# micro_motor.net
KiCad netlist of a schematic drawn in EAGLE
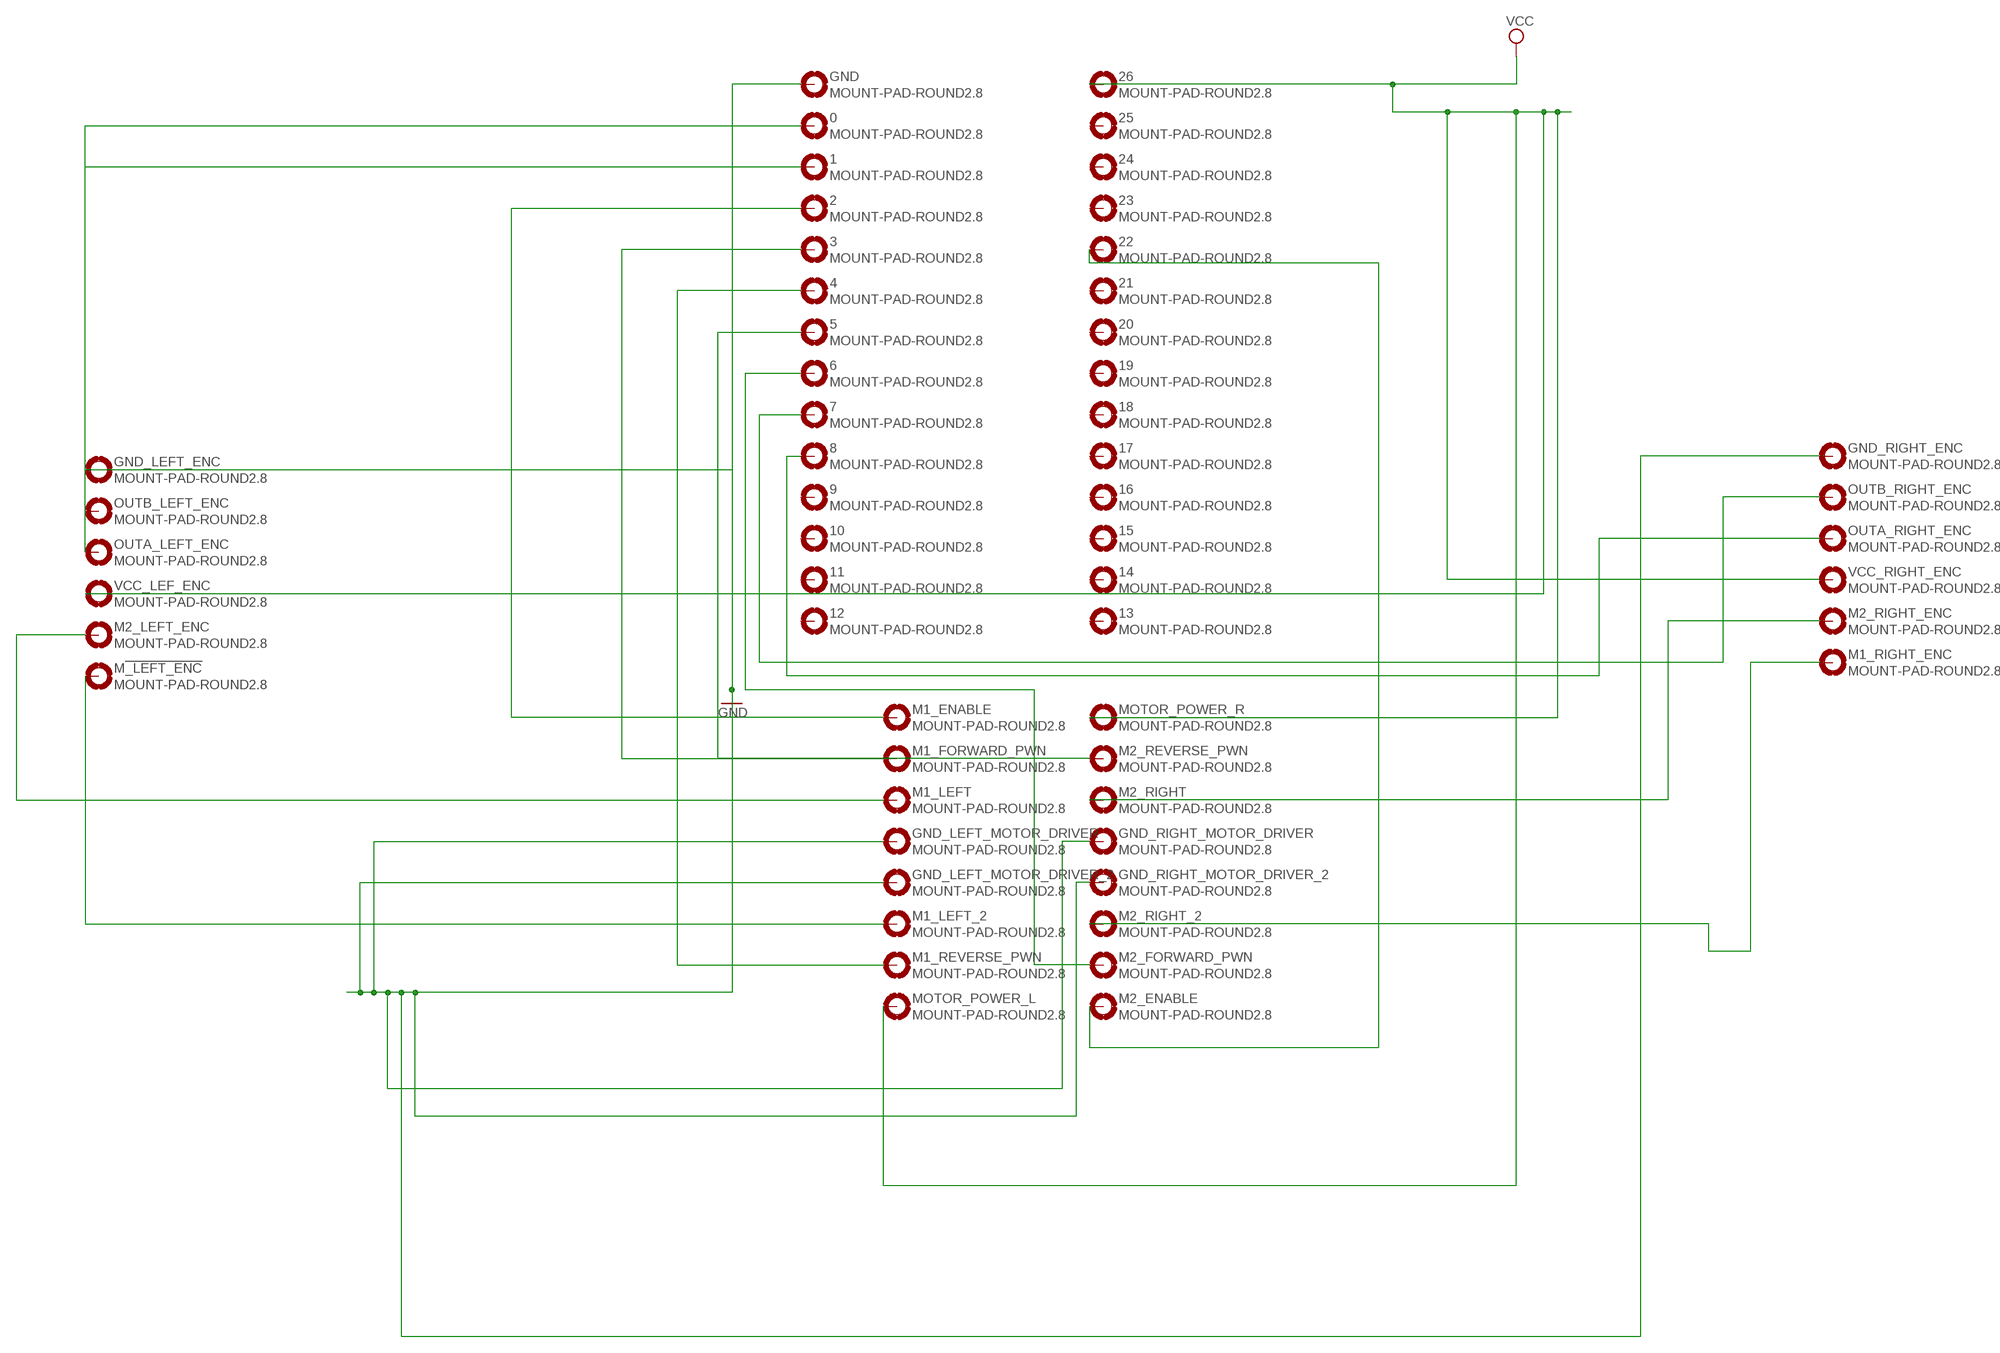
[diagram p0: schematic, sheet 1]

(export (version "E")
  (design (tool "Eeschema 10.0.6"))
  (components
    (comp (ref "0")
      (value "MOUNT-PAD-ROUND2.8")
      (footprint "eagle-import:2,8-PAD")
      (libsource (lib "eagle-import") (part "MOUNT-PAD-ROUND2.8"))
    )
    (comp (ref "1")
      (value "MOUNT-PAD-ROUND2.8")
      (footprint "eagle-import:2,8-PAD")
      (libsource (lib "eagle-import") (part "MOUNT-PAD-ROUND2.8"))
    )
    (comp (ref "2")
      (value "MOUNT-PAD-ROUND2.8")
      (footprint "eagle-import:2,8-PAD")
      (libsource (lib "eagle-import") (part "MOUNT-PAD-ROUND2.8"))
    )
    (comp (ref "3")
      (value "MOUNT-PAD-ROUND2.8")
      (footprint "eagle-import:2,8-PAD")
      (libsource (lib "eagle-import") (part "MOUNT-PAD-ROUND2.8"))
    )
    (comp (ref "4")
      (value "MOUNT-PAD-ROUND2.8")
      (footprint "eagle-import:2,8-PAD")
      (libsource (lib "eagle-import") (part "MOUNT-PAD-ROUND2.8"))
    )
    (comp (ref "5")
      (value "MOUNT-PAD-ROUND2.8")
      (footprint "eagle-import:2,8-PAD")
      (libsource (lib "eagle-import") (part "MOUNT-PAD-ROUND2.8"))
    )
    (comp (ref "6")
      (value "MOUNT-PAD-ROUND2.8")
      (footprint "eagle-import:2,8-PAD")
      (libsource (lib "eagle-import") (part "MOUNT-PAD-ROUND2.8"))
    )
    (comp (ref "7")
      (value "MOUNT-PAD-ROUND2.8")
      (footprint "eagle-import:2,8-PAD")
      (libsource (lib "eagle-import") (part "MOUNT-PAD-ROUND2.8"))
    )
    (comp (ref "8")
      (value "MOUNT-PAD-ROUND2.8")
      (footprint "eagle-import:2,8-PAD")
      (libsource (lib "eagle-import") (part "MOUNT-PAD-ROUND2.8"))
    )
    (comp (ref "9")
      (value "MOUNT-PAD-ROUND2.8")
      (footprint "eagle-import:2,8-PAD")
      (libsource (lib "eagle-import") (part "MOUNT-PAD-ROUND2.8"))
    )
    (comp (ref "10")
      (value "MOUNT-PAD-ROUND2.8")
      (footprint "eagle-import:2,8-PAD")
      (libsource (lib "eagle-import") (part "MOUNT-PAD-ROUND2.8"))
    )
    (comp (ref "11")
      (value "MOUNT-PAD-ROUND2.8")
      (footprint "eagle-import:2,8-PAD")
      (libsource (lib "eagle-import") (part "MOUNT-PAD-ROUND2.8"))
    )
    (comp (ref "12")
      (value "MOUNT-PAD-ROUND2.8")
      (footprint "eagle-import:2,8-PAD")
      (libsource (lib "eagle-import") (part "MOUNT-PAD-ROUND2.8"))
    )
    (comp (ref "13")
      (value "MOUNT-PAD-ROUND2.8")
      (footprint "eagle-import:2,8-PAD")
      (libsource (lib "eagle-import") (part "MOUNT-PAD-ROUND2.8"))
    )
    (comp (ref "14")
      (value "MOUNT-PAD-ROUND2.8")
      (footprint "eagle-import:2,8-PAD")
      (libsource (lib "eagle-import") (part "MOUNT-PAD-ROUND2.8"))
    )
    (comp (ref "15")
      (value "MOUNT-PAD-ROUND2.8")
      (footprint "eagle-import:2,8-PAD")
      (libsource (lib "eagle-import") (part "MOUNT-PAD-ROUND2.8"))
    )
    (comp (ref "16")
      (value "MOUNT-PAD-ROUND2.8")
      (footprint "eagle-import:2,8-PAD")
      (libsource (lib "eagle-import") (part "MOUNT-PAD-ROUND2.8"))
    )
    (comp (ref "17")
      (value "MOUNT-PAD-ROUND2.8")
      (footprint "eagle-import:2,8-PAD")
      (libsource (lib "eagle-import") (part "MOUNT-PAD-ROUND2.8"))
    )
    (comp (ref "18")
      (value "MOUNT-PAD-ROUND2.8")
      (footprint "eagle-import:2,8-PAD")
      (libsource (lib "eagle-import") (part "MOUNT-PAD-ROUND2.8"))
    )
    (comp (ref "19")
      (value "MOUNT-PAD-ROUND2.8")
      (footprint "eagle-import:2,8-PAD")
      (libsource (lib "eagle-import") (part "MOUNT-PAD-ROUND2.8"))
    )
    (comp (ref "20")
      (value "MOUNT-PAD-ROUND2.8")
      (footprint "eagle-import:2,8-PAD")
      (libsource (lib "eagle-import") (part "MOUNT-PAD-ROUND2.8"))
    )
    (comp (ref "21")
      (value "MOUNT-PAD-ROUND2.8")
      (footprint "eagle-import:2,8-PAD")
      (libsource (lib "eagle-import") (part "MOUNT-PAD-ROUND2.8"))
    )
    (comp (ref "22")
      (value "MOUNT-PAD-ROUND2.8")
      (footprint "eagle-import:2,8-PAD")
      (libsource (lib "eagle-import") (part "MOUNT-PAD-ROUND2.8"))
    )
    (comp (ref "23")
      (value "MOUNT-PAD-ROUND2.8")
      (footprint "eagle-import:2,8-PAD")
      (libsource (lib "eagle-import") (part "MOUNT-PAD-ROUND2.8"))
    )
    (comp (ref "24")
      (value "MOUNT-PAD-ROUND2.8")
      (footprint "eagle-import:2,8-PAD")
      (libsource (lib "eagle-import") (part "MOUNT-PAD-ROUND2.8"))
    )
    (comp (ref "25")
      (value "MOUNT-PAD-ROUND2.8")
      (footprint "eagle-import:2,8-PAD")
      (libsource (lib "eagle-import") (part "MOUNT-PAD-ROUND2.8"))
    )
    (comp (ref "26")
      (value "MOUNT-PAD-ROUND2.8")
      (footprint "eagle-import:2,8-PAD")
      (libsource (lib "eagle-import") (part "MOUNT-PAD-ROUND2.8"))
    )
    (comp (ref "GND")
      (value "MOUNT-PAD-ROUND2.8")
      (footprint "eagle-import:2,8-PAD")
      (libsource (lib "eagle-import") (part "MOUNT-PAD-ROUND2.8"))
    )
    (comp (ref "GND_LEFT_ENC")
      (value "MOUNT-PAD-ROUND2.8")
      (footprint "eagle-import:2,8-PAD")
      (libsource (lib "eagle-import") (part "MOUNT-PAD-ROUND2.8"))
    )
    (comp (ref "GND_LEFT_MOTOR_DRIVER")
      (value "MOUNT-PAD-ROUND2.8")
      (footprint "eagle-import:2,8-PAD")
      (libsource (lib "eagle-import") (part "MOUNT-PAD-ROUND2.8"))
    )
    (comp (ref "GND_LEFT_MOTOR_DRIVER_2")
      (value "MOUNT-PAD-ROUND2.8")
      (footprint "eagle-import:2,8-PAD")
      (libsource (lib "eagle-import") (part "MOUNT-PAD-ROUND2.8"))
    )
    (comp (ref "GND_RIGHT_ENC")
      (value "MOUNT-PAD-ROUND2.8")
      (footprint "eagle-import:2,8-PAD")
      (libsource (lib "eagle-import") (part "MOUNT-PAD-ROUND2.8"))
    )
    (comp (ref "GND_RIGHT_MOTOR_DRIVER")
      (value "MOUNT-PAD-ROUND2.8")
      (footprint "eagle-import:2,8-PAD")
      (libsource (lib "eagle-import") (part "MOUNT-PAD-ROUND2.8"))
    )
    (comp (ref "GND_RIGHT_MOTOR_DRIVER_2")
      (value "MOUNT-PAD-ROUND2.8")
      (footprint "eagle-import:2,8-PAD")
      (libsource (lib "eagle-import") (part "MOUNT-PAD-ROUND2.8"))
    )
    (comp (ref "M!_LEFT_ENC")
      (value "MOUNT-PAD-ROUND2.8")
      (footprint "eagle-import:2,8-PAD")
      (libsource (lib "eagle-import") (part "MOUNT-PAD-ROUND2.8"))
    )
    (comp (ref "M1_ENABLE")
      (value "MOUNT-PAD-ROUND2.8")
      (footprint "eagle-import:2,8-PAD")
      (libsource (lib "eagle-import") (part "MOUNT-PAD-ROUND2.8"))
    )
    (comp (ref "M1_FORWARD_PWN")
      (value "MOUNT-PAD-ROUND2.8")
      (footprint "eagle-import:2,8-PAD")
      (libsource (lib "eagle-import") (part "MOUNT-PAD-ROUND2.8"))
    )
    (comp (ref "M1_LEFT")
      (value "MOUNT-PAD-ROUND2.8")
      (footprint "eagle-import:2,8-PAD")
      (libsource (lib "eagle-import") (part "MOUNT-PAD-ROUND2.8"))
    )
    (comp (ref "M1_LEFT_2")
      (value "MOUNT-PAD-ROUND2.8")
      (footprint "eagle-import:2,8-PAD")
      (libsource (lib "eagle-import") (part "MOUNT-PAD-ROUND2.8"))
    )
    (comp (ref "M1_REVERSE_PWN")
      (value "MOUNT-PAD-ROUND2.8")
      (footprint "eagle-import:2,8-PAD")
      (libsource (lib "eagle-import") (part "MOUNT-PAD-ROUND2.8"))
    )
    (comp (ref "M1_RIGHT_ENC")
      (value "MOUNT-PAD-ROUND2.8")
      (footprint "eagle-import:2,8-PAD")
      (libsource (lib "eagle-import") (part "MOUNT-PAD-ROUND2.8"))
    )
    (comp (ref "M2_ENABLE")
      (value "MOUNT-PAD-ROUND2.8")
      (footprint "eagle-import:2,8-PAD")
      (libsource (lib "eagle-import") (part "MOUNT-PAD-ROUND2.8"))
    )
    (comp (ref "M2_FORWARD_PWN")
      (value "MOUNT-PAD-ROUND2.8")
      (footprint "eagle-import:2,8-PAD")
      (libsource (lib "eagle-import") (part "MOUNT-PAD-ROUND2.8"))
    )
    (comp (ref "M2_LEFT_ENC")
      (value "MOUNT-PAD-ROUND2.8")
      (footprint "eagle-import:2,8-PAD")
      (libsource (lib "eagle-import") (part "MOUNT-PAD-ROUND2.8"))
    )
    (comp (ref "M2_REVERSE_PWN")
      (value "MOUNT-PAD-ROUND2.8")
      (footprint "eagle-import:2,8-PAD")
      (libsource (lib "eagle-import") (part "MOUNT-PAD-ROUND2.8"))
    )
    (comp (ref "M2_RIGHT")
      (value "MOUNT-PAD-ROUND2.8")
      (footprint "eagle-import:2,8-PAD")
      (libsource (lib "eagle-import") (part "MOUNT-PAD-ROUND2.8"))
    )
    (comp (ref "M2_RIGHT_2")
      (value "MOUNT-PAD-ROUND2.8")
      (footprint "eagle-import:2,8-PAD")
      (libsource (lib "eagle-import") (part "MOUNT-PAD-ROUND2.8"))
    )
    (comp (ref "M2_RIGHT_ENC")
      (value "MOUNT-PAD-ROUND2.8")
      (footprint "eagle-import:2,8-PAD")
      (libsource (lib "eagle-import") (part "MOUNT-PAD-ROUND2.8"))
    )
    (comp (ref "MOTOR_POWER_L")
      (value "MOUNT-PAD-ROUND2.8")
      (footprint "eagle-import:2,8-PAD")
      (libsource (lib "eagle-import") (part "MOUNT-PAD-ROUND2.8"))
    )
    (comp (ref "MOTOR_POWER_R")
      (value "MOUNT-PAD-ROUND2.8")
      (footprint "eagle-import:2,8-PAD")
      (libsource (lib "eagle-import") (part "MOUNT-PAD-ROUND2.8"))
    )
    (comp (ref "OUTA_LEFT_ENC")
      (value "MOUNT-PAD-ROUND2.8")
      (footprint "eagle-import:2,8-PAD")
      (libsource (lib "eagle-import") (part "MOUNT-PAD-ROUND2.8"))
    )
    (comp (ref "OUTA_RIGHT_ENC")
      (value "MOUNT-PAD-ROUND2.8")
      (footprint "eagle-import:2,8-PAD")
      (libsource (lib "eagle-import") (part "MOUNT-PAD-ROUND2.8"))
    )
    (comp (ref "OUTB_LEFT_ENC")
      (value "MOUNT-PAD-ROUND2.8")
      (footprint "eagle-import:2,8-PAD")
      (libsource (lib "eagle-import") (part "MOUNT-PAD-ROUND2.8"))
    )
    (comp (ref "OUTB_RIGHT_ENC")
      (value "MOUNT-PAD-ROUND2.8")
      (footprint "eagle-import:2,8-PAD")
      (libsource (lib "eagle-import") (part "MOUNT-PAD-ROUND2.8"))
    )
    (comp (ref "VCC_LEF_ENC")
      (value "MOUNT-PAD-ROUND2.8")
      (footprint "eagle-import:2,8-PAD")
      (libsource (lib "eagle-import") (part "MOUNT-PAD-ROUND2.8"))
    )
    (comp (ref "VCC_RIGHT_ENC")
      (value "MOUNT-PAD-ROUND2.8")
      (footprint "eagle-import:2,8-PAD")
      (libsource (lib "eagle-import") (part "MOUNT-PAD-ROUND2.8"))
    )
  )
  (nets
    (net (code "1") (name "GND") (class "Default")
      (node (ref "GND") (pin "B2,8") (pinfunction "MOUNT_B2,8") (pintype "passive"))
      (node (ref "GND_LEFT_ENC") (pin "B2,8") (pinfunction "MOUNT_B2,8") (pintype "passive"))
      (node (ref "GND_LEFT_MOTOR_DRIVER") (pin "B2,8") (pinfunction "MOUNT_B2,8") (pintype "passive"))
      (node (ref "GND_LEFT_MOTOR_DRIVER_2") (pin "B2,8") (pinfunction "MOUNT_B2,8") (pintype "passive"))
      (node (ref "GND_RIGHT_ENC") (pin "B2,8") (pinfunction "MOUNT_B2,8") (pintype "passive"))
      (node (ref "GND_RIGHT_MOTOR_DRIVER") (pin "B2,8") (pinfunction "MOUNT_B2,8") (pintype "passive"))
      (node (ref "GND_RIGHT_MOTOR_DRIVER_2") (pin "B2,8") (pinfunction "MOUNT_B2,8") (pintype "passive"))
    )
    (net (code "2") (name "Net-(0-MOUNT)") (class "Default")
      (node (ref "0") (pin "B2,8") (pinfunction "MOUNT_B2,8") (pintype "passive"))
      (node (ref "OUTB_LEFT_ENC") (pin "B2,8") (pinfunction "MOUNT_B2,8") (pintype "passive"))
    )
    (net (code "3") (name "Net-(1-MOUNT)") (class "Default")
      (node (ref "1") (pin "B2,8") (pinfunction "MOUNT_B2,8") (pintype "passive"))
      (node (ref "OUTA_LEFT_ENC") (pin "B2,8") (pinfunction "MOUNT_B2,8") (pintype "passive"))
    )
    (net (code "4") (name "Net-(2-MOUNT)") (class "Default")
      (node (ref "2") (pin "B2,8") (pinfunction "MOUNT_B2,8") (pintype "passive"))
      (node (ref "M1_ENABLE") (pin "B2,8") (pinfunction "MOUNT_B2,8") (pintype "passive"))
    )
    (net (code "5") (name "Net-(3-MOUNT)") (class "Default")
      (node (ref "3") (pin "B2,8") (pinfunction "MOUNT_B2,8") (pintype "passive"))
      (node (ref "M1_FORWARD_PWN") (pin "B2,8") (pinfunction "MOUNT_B2,8") (pintype "passive"))
    )
    (net (code "6") (name "Net-(4-MOUNT)") (class "Default")
      (node (ref "4") (pin "B2,8") (pinfunction "MOUNT_B2,8") (pintype "passive"))
      (node (ref "M1_REVERSE_PWN") (pin "B2,8") (pinfunction "MOUNT_B2,8") (pintype "passive"))
    )
    (net (code "7") (name "Net-(5-MOUNT)") (class "Default")
      (node (ref "5") (pin "B2,8") (pinfunction "MOUNT_B2,8") (pintype "passive"))
      (node (ref "M2_REVERSE_PWN") (pin "B2,8") (pinfunction "MOUNT_B2,8") (pintype "passive"))
    )
    (net (code "8") (name "Net-(6-MOUNT)") (class "Default")
      (node (ref "6") (pin "B2,8") (pinfunction "MOUNT_B2,8") (pintype "passive"))
      (node (ref "M2_FORWARD_PWN") (pin "B2,8") (pinfunction "MOUNT_B2,8") (pintype "passive"))
    )
    (net (code "9") (name "Net-(7-MOUNT)") (class "Default")
      (node (ref "7") (pin "B2,8") (pinfunction "MOUNT_B2,8") (pintype "passive"))
      (node (ref "OUTB_RIGHT_ENC") (pin "B2,8") (pinfunction "MOUNT_B2,8") (pintype "passive"))
    )
    (net (code "10") (name "Net-(8-MOUNT)") (class "Default")
      (node (ref "8") (pin "B2,8") (pinfunction "MOUNT_B2,8") (pintype "passive"))
      (node (ref "OUTA_RIGHT_ENC") (pin "B2,8") (pinfunction "MOUNT_B2,8") (pintype "passive"))
    )
    (net (code "11") (name "Net-(22-MOUNT)") (class "Default")
      (node (ref "22") (pin "B2,8") (pinfunction "MOUNT_B2,8") (pintype "passive"))
      (node (ref "M2_ENABLE") (pin "B2,8") (pinfunction "MOUNT_B2,8") (pintype "passive"))
    )
    (net (code "12") (name "Net-(M!_LEFT_ENC-MOUNT)") (class "Default")
      (node (ref "M!_LEFT_ENC") (pin "B2,8") (pinfunction "MOUNT_B2,8") (pintype "passive"))
      (node (ref "M1_LEFT_2") (pin "B2,8") (pinfunction "MOUNT_B2,8") (pintype "passive"))
    )
    (net (code "13") (name "Net-(M1_LEFT-MOUNT)") (class "Default")
      (node (ref "M1_LEFT") (pin "B2,8") (pinfunction "MOUNT_B2,8") (pintype "passive"))
      (node (ref "M2_LEFT_ENC") (pin "B2,8") (pinfunction "MOUNT_B2,8") (pintype "passive"))
    )
    (net (code "14") (name "Net-(M1_RIGHT_ENC-MOUNT)") (class "Default")
      (node (ref "M1_RIGHT_ENC") (pin "B2,8") (pinfunction "MOUNT_B2,8") (pintype "passive"))
      (node (ref "M2_RIGHT_2") (pin "B2,8") (pinfunction "MOUNT_B2,8") (pintype "passive"))
    )
    (net (code "15") (name "Net-(M2_RIGHT-MOUNT)") (class "Default")
      (node (ref "M2_RIGHT") (pin "B2,8") (pinfunction "MOUNT_B2,8") (pintype "passive"))
      (node (ref "M2_RIGHT_ENC") (pin "B2,8") (pinfunction "MOUNT_B2,8") (pintype "passive"))
    )
    (net (code "16") (name "VCC") (class "Default")
      (node (ref "26") (pin "B2,8") (pinfunction "MOUNT_B2,8") (pintype "passive"))
      (node (ref "MOTOR_POWER_L") (pin "B2,8") (pinfunction "MOUNT_B2,8") (pintype "passive"))
      (node (ref "MOTOR_POWER_R") (pin "B2,8") (pinfunction "MOUNT_B2,8") (pintype "passive"))
      (node (ref "VCC_LEF_ENC") (pin "B2,8") (pinfunction "MOUNT_B2,8") (pintype "passive"))
      (node (ref "VCC_RIGHT_ENC") (pin "B2,8") (pinfunction "MOUNT_B2,8") (pintype "passive"))
    )
    (net (code "17") (name "unconnected-(9-MOUNT-PadB2,8)") (class "Default")
      (node (ref "9") (pin "B2,8") (pinfunction "MOUNT_B2,8") (pintype "passive"))
    )
    (net (code "18") (name "unconnected-(10-MOUNT-PadB2,8)") (class "Default")
      (node (ref "10") (pin "B2,8") (pinfunction "MOUNT_B2,8") (pintype "passive"))
    )
    (net (code "19") (name "unconnected-(11-MOUNT-PadB2,8)") (class "Default")
      (node (ref "11") (pin "B2,8") (pinfunction "MOUNT_B2,8") (pintype "passive"))
    )
    (net (code "20") (name "unconnected-(12-MOUNT-PadB2,8)") (class "Default")
      (node (ref "12") (pin "B2,8") (pinfunction "MOUNT_B2,8") (pintype "passive"))
    )
    (net (code "21") (name "unconnected-(13-MOUNT-PadB2,8)") (class "Default")
      (node (ref "13") (pin "B2,8") (pinfunction "MOUNT_B2,8") (pintype "passive"))
    )
    (net (code "22") (name "unconnected-(14-MOUNT-PadB2,8)") (class "Default")
      (node (ref "14") (pin "B2,8") (pinfunction "MOUNT_B2,8") (pintype "passive"))
    )
    (net (code "23") (name "unconnected-(15-MOUNT-PadB2,8)") (class "Default")
      (node (ref "15") (pin "B2,8") (pinfunction "MOUNT_B2,8") (pintype "passive"))
    )
    (net (code "24") (name "unconnected-(16-MOUNT-PadB2,8)") (class "Default")
      (node (ref "16") (pin "B2,8") (pinfunction "MOUNT_B2,8") (pintype "passive"))
    )
    (net (code "25") (name "unconnected-(17-MOUNT-PadB2,8)") (class "Default")
      (node (ref "17") (pin "B2,8") (pinfunction "MOUNT_B2,8") (pintype "passive"))
    )
    (net (code "26") (name "unconnected-(18-MOUNT-PadB2,8)") (class "Default")
      (node (ref "18") (pin "B2,8") (pinfunction "MOUNT_B2,8") (pintype "passive"))
    )
    (net (code "27") (name "unconnected-(19-MOUNT-PadB2,8)") (class "Default")
      (node (ref "19") (pin "B2,8") (pinfunction "MOUNT_B2,8") (pintype "passive"))
    )
    (net (code "28") (name "unconnected-(20-MOUNT-PadB2,8)") (class "Default")
      (node (ref "20") (pin "B2,8") (pinfunction "MOUNT_B2,8") (pintype "passive"))
    )
    (net (code "29") (name "unconnected-(21-MOUNT-PadB2,8)") (class "Default")
      (node (ref "21") (pin "B2,8") (pinfunction "MOUNT_B2,8") (pintype "passive"))
    )
    (net (code "30") (name "unconnected-(23-MOUNT-PadB2,8)") (class "Default")
      (node (ref "23") (pin "B2,8") (pinfunction "MOUNT_B2,8") (pintype "passive"))
    )
    (net (code "31") (name "unconnected-(24-MOUNT-PadB2,8)") (class "Default")
      (node (ref "24") (pin "B2,8") (pinfunction "MOUNT_B2,8") (pintype "passive"))
    )
    (net (code "32") (name "unconnected-(25-MOUNT-PadB2,8)") (class "Default")
      (node (ref "25") (pin "B2,8") (pinfunction "MOUNT_B2,8") (pintype "passive"))
    )
  )
)
